# rgb-led-a.net
KiCad netlist of a schematic drawn in EAGLE
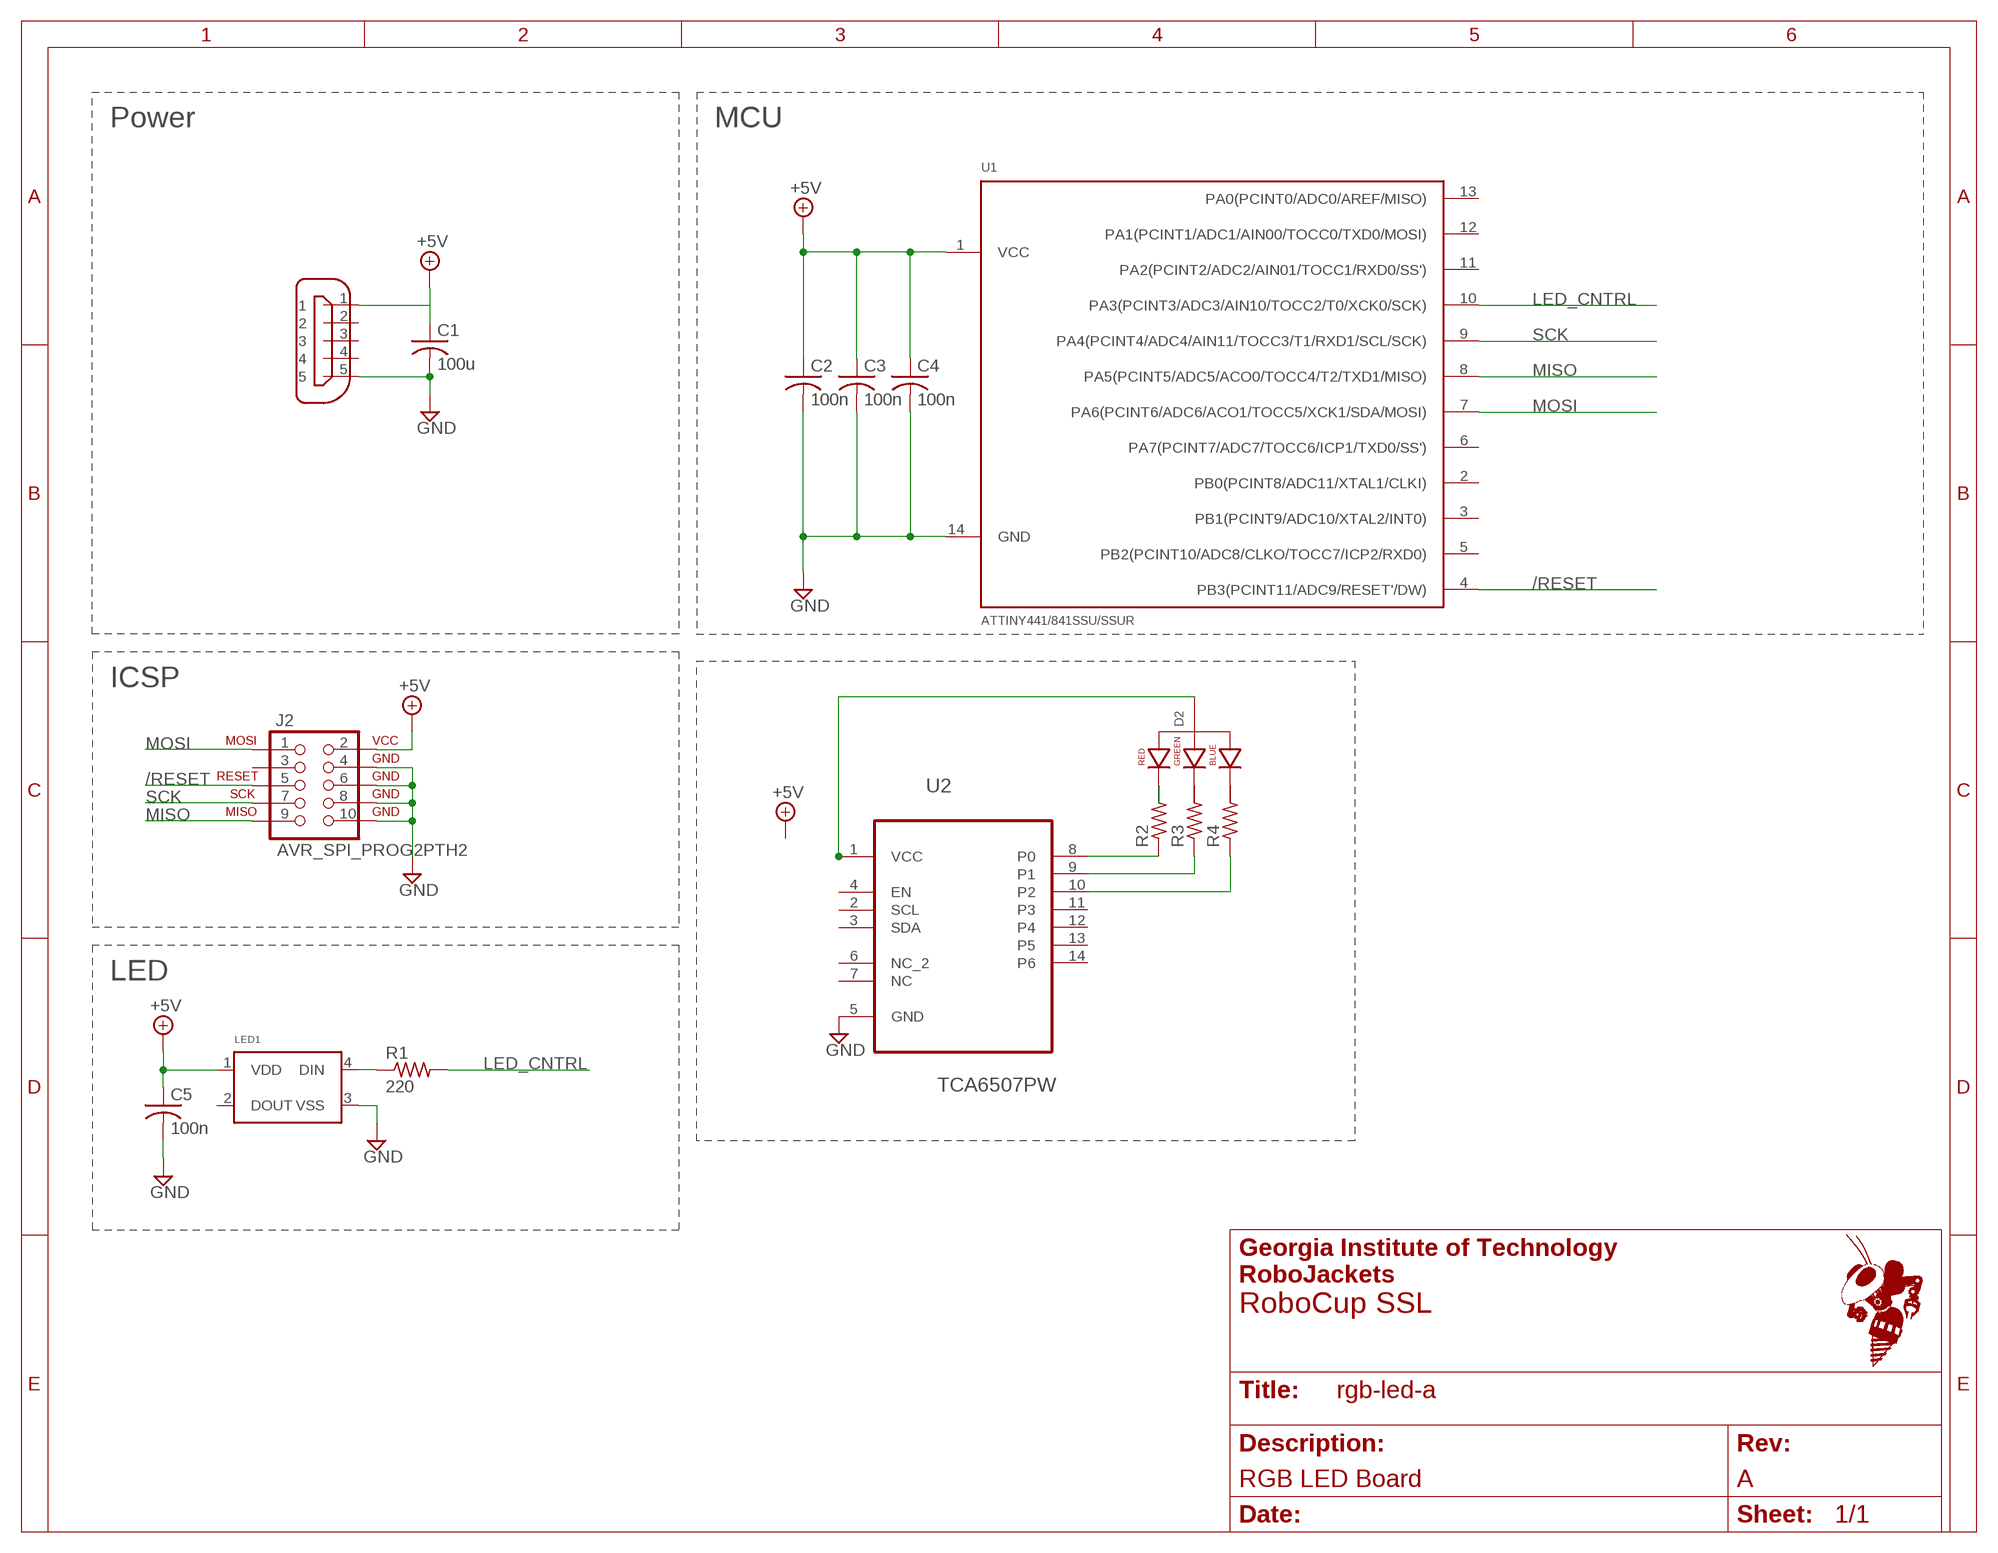
[diagram p0: schematic, sheet 1]

(export (version "E")
  (design (tool "Eeschema 10.0.6"))
  (components
    (comp (ref "C1")
      (value "100u")
      (footprint "eagle-import:C1206")
      (libsource (lib "eagle-import") (part "C-USC1206"))
    )
    (comp (ref "C2")
      (value "100n")
      (footprint "eagle-import:C0603")
      (libsource (lib "eagle-import") (part "C-USC0603"))
    )
    (comp (ref "C3")
      (value "100n")
      (footprint "eagle-import:C0603")
      (libsource (lib "eagle-import") (part "C-USC0603"))
    )
    (comp (ref "C4")
      (value "100n")
      (footprint "eagle-import:C0603")
      (libsource (lib "eagle-import") (part "C-USC0603"))
    )
    (comp (ref "C5")
      (value "100n")
      (footprint "eagle-import:C0603")
      (libsource (lib "eagle-import") (part "C-USC0603"))
    )
    (comp (ref "D2")
      (value "LED-RGB-CA-THRUCLEAR")
      (footprint "eagle-import:LED-RGB-THRU")
      (libsource (lib "eagle-import") (part "LED-RGB-CA-THRUCLEAR"))
    )
    (comp (ref "J1")
      (value "MICRO-USB")
      (footprint "eagle-import:GS-14-2180")
      (libsource (lib "eagle-import") (part "MICRO-USB"))
    )
    (comp (ref "J2")
      (value "AVR_SPI_PROG2PTH2")
      (footprint "eagle-import:2X5-SHROUDED")
      (libsource (lib "eagle-import") (part "AVR_SPI_PROG2PTH2"))
    )
    (comp (ref "LED1")
      (value "WS2812B")
      (footprint "eagle-import:5050")
      (libsource (lib "eagle-import") (part "WS2812B"))
    )
    (comp (ref "R1")
      (value "220")
      (footprint "eagle-import:R0603")
      (libsource (lib "eagle-import") (part "R-US_R0603"))
    )
    (comp (ref "R2")
      (value "R-US_R0805")
      (footprint "eagle-import:R0805")
      (libsource (lib "eagle-import") (part "resistor_R-US_R0805"))
    )
    (comp (ref "R3")
      (value "R-US_R0805")
      (footprint "eagle-import:R0805")
      (libsource (lib "eagle-import") (part "resistor_R-US_R0805"))
    )
    (comp (ref "R4")
      (value "R-US_R0805")
      (footprint "eagle-import:R0805")
      (libsource (lib "eagle-import") (part "resistor_R-US_R0805"))
    )
    (comp (ref "U1")
      (value "ATTINY441/841SSU/SSUR")
      (footprint "eagle-import:SOIC-14")
      (libsource (lib "eagle-import") (part "ATTINY441/841SSU/SSUR"))
    )
    (comp (ref "U2")
      (value "TCA6507PW")
      (footprint "eagle-import:SOP65P640X120-14N")
      (libsource (lib "eagle-import") (part "TCA6507PW"))
    )
  )
  (nets
    (net (code "1") (name "+5V") (class "Default")
      (node (ref "C1") (pin "1") (pinfunction "1_1") (pintype "passive"))
      (node (ref "C2") (pin "1") (pinfunction "1_1") (pintype "passive"))
      (node (ref "C3") (pin "1") (pinfunction "1_1") (pintype "passive"))
      (node (ref "C4") (pin "1") (pinfunction "1_1") (pintype "passive"))
      (node (ref "C5") (pin "1") (pinfunction "1_1") (pintype "passive"))
      (node (ref "J1") (pin "1") (pinfunction "1_1") (pintype "bidirectional"))
      (node (ref "J2") (pin "2") (pinfunction "VCC_2") (pintype "power_in"))
      (node (ref "LED1") (pin "1") (pinfunction "VDD_1") (pintype "bidirectional"))
      (node (ref "U1") (pin "1") (pinfunction "VCC_1") (pintype "bidirectional"))
    )
    (net (code "2") (name "/LED_CNTRL") (class "Default")
      (node (ref "R1") (pin "2") (pinfunction "2_2") (pintype "passive"))
      (node (ref "U1") (pin "10") (pinfunction "PA3(PCINT3/ADC3/AIN10/TOCC2/T0/XCK0/SCK)_10") (pintype "bidirectional"))
    )
    (net (code "3") (name "/MISO") (class "Default")
      (node (ref "J2") (pin "9") (pinfunction "MISO_9") (pintype "passive"))
      (node (ref "U1") (pin "8") (pinfunction "PA5(PCINT5/ADC5/ACO0/TOCC4/T2/TXD1/MISO)_8") (pintype "bidirectional"))
    )
    (net (code "4") (name "/MOSI") (class "Default")
      (node (ref "J2") (pin "1") (pinfunction "MOSI_1") (pintype "passive"))
      (node (ref "U1") (pin "7") (pinfunction "PA6(PCINT6/ADC6/ACO1/TOCC5/XCK1/SDA/MOSI)_7") (pintype "bidirectional"))
    )
    (net (code "5") (name "/SCK") (class "Default")
      (node (ref "J2") (pin "7") (pinfunction "SCK_7") (pintype "passive"))
      (node (ref "U1") (pin "9") (pinfunction "PA4(PCINT4/ADC4/AIN11/TOCC3/T1/RXD1/SCL/SCK)_9") (pintype "bidirectional"))
    )
    (net (code "6") (name "/{slash}RESET") (class "Default")
      (node (ref "J2") (pin "5") (pinfunction "RESET_5") (pintype "passive"))
      (node (ref "U1") (pin "4") (pinfunction "PB3(PCINT11/ADC9/RESET'/DW)_4") (pintype "bidirectional"))
    )
    (net (code "7") (name "GND") (class "Default")
      (node (ref "C1") (pin "2") (pinfunction "2_2") (pintype "passive"))
      (node (ref "C2") (pin "2") (pinfunction "2_2") (pintype "passive"))
      (node (ref "C3") (pin "2") (pinfunction "2_2") (pintype "passive"))
      (node (ref "C4") (pin "2") (pinfunction "2_2") (pintype "passive"))
      (node (ref "C5") (pin "2") (pinfunction "2_2") (pintype "passive"))
      (node (ref "J1") (pin "5") (pinfunction "5_5") (pintype "bidirectional"))
      (node (ref "J2") (pin "10") (pinfunction "GND_10") (pintype "power_in"))
      (node (ref "J2") (pin "4") (pinfunction "GND_4") (pintype "power_in"))
      (node (ref "J2") (pin "6") (pinfunction "GND_6") (pintype "power_in"))
      (node (ref "J2") (pin "8") (pinfunction "GND_8") (pintype "power_in"))
      (node (ref "LED1") (pin "3") (pinfunction "VSS_3") (pintype "bidirectional"))
      (node (ref "U1") (pin "14") (pinfunction "GND_14") (pintype "bidirectional"))
      (node (ref "U2") (pin "5") (pinfunction "GND_5") (pintype "passive"))
    )
    (net (code "8") (name "Net-(D2-ANODE)") (class "Default")
      (node (ref "D2") (pin "2") (pinfunction "ANODE_2") (pintype "bidirectional"))
      (node (ref "U2") (pin "1") (pinfunction "VCC_1") (pintype "power_in"))
    )
    (net (code "9") (name "Net-(D2-RED_CATHODE)") (class "Default")
      (node (ref "D2") (pin "1") (pinfunction "RED_CATHODE_1") (pintype "bidirectional"))
      (node (ref "R2") (pin "2") (pinfunction "2_2") (pintype "passive"))
    )
    (net (code "10") (name "Net-(LED1-DIN)") (class "Default")
      (node (ref "LED1") (pin "4") (pinfunction "DIN_4") (pintype "bidirectional"))
      (node (ref "R1") (pin "1") (pinfunction "1_1") (pintype "passive"))
    )
    (net (code "11") (name "Net-(U2-P0)") (class "Default")
      (node (ref "R2") (pin "1") (pinfunction "1_1") (pintype "passive"))
      (node (ref "U2") (pin "8") (pinfunction "P0_8") (pintype "output"))
    )
    (net (code "12") (name "Net-(U2-P1)") (class "Default")
      (node (ref "R3") (pin "1") (pinfunction "1_1") (pintype "passive"))
      (node (ref "U2") (pin "9") (pinfunction "P1_9") (pintype "output"))
    )
    (net (code "13") (name "Net-(U2-P2)") (class "Default")
      (node (ref "R4") (pin "1") (pinfunction "1_1") (pintype "passive"))
      (node (ref "U2") (pin "10") (pinfunction "P2_10") (pintype "output"))
    )
    (net (code "14") (name "unconnected-(D2-BLUE_CATHODE-Pad4)") (class "Default")
      (node (ref "D2") (pin "4") (pinfunction "BLUE_CATHODE_4") (pintype "bidirectional"))
    )
    (net (code "15") (name "unconnected-(D2-GREEN_CATHODE-Pad3)") (class "Default")
      (node (ref "D2") (pin "3") (pinfunction "GREEN_CATHODE_3") (pintype "bidirectional"))
    )
    (net (code "16") (name "unconnected-(J1-Pad2)") (class "Default")
      (node (ref "J1") (pin "2") (pinfunction "2_2") (pintype "bidirectional"))
    )
    (net (code "17") (name "unconnected-(J1-Pad3)") (class "Default")
      (node (ref "J1") (pin "3") (pinfunction "3_3") (pintype "bidirectional"))
    )
    (net (code "18") (name "unconnected-(J1-Pad4)") (class "Default")
      (node (ref "J1") (pin "4") (pinfunction "4_4") (pintype "bidirectional"))
    )
    (net (code "19") (name "unconnected-(J2-NC-Pad3)") (class "Default")
      (node (ref "J2") (pin "3") (pinfunction "NC_3") (pintype "no_connect"))
    )
    (net (code "20") (name "unconnected-(LED1-DOUT-Pad2)") (class "Default")
      (node (ref "LED1") (pin "2") (pinfunction "DOUT_2") (pintype "bidirectional"))
    )
    (net (code "21") (name "unconnected-(R3-Pad2)") (class "Default")
      (node (ref "R3") (pin "2") (pinfunction "2_2") (pintype "passive"))
    )
    (net (code "22") (name "unconnected-(R4-Pad2)") (class "Default")
      (node (ref "R4") (pin "2") (pinfunction "2_2") (pintype "passive"))
    )
    (net (code "23") (name "unconnected-(U1-PA0(PCINT0{slash}ADC0{slash}AREF{slash}MISO)-Pad13)") (class "Default")
      (node (ref "U1") (pin "13") (pinfunction "PA0(PCINT0/ADC0/AREF/MISO)_13") (pintype "bidirectional"))
    )
    (net (code "24") (name "unconnected-(U1-PA1(PCINT1{slash}ADC1{slash}AIN00{slash}TOCC0{slash}TXD0{slash}MOSI)-Pad12)") (class "Default")
      (node (ref "U1") (pin "12") (pinfunction "PA1(PCINT1/ADC1/AIN00/TOCC0/TXD0/MOSI)_12") (pintype "bidirectional"))
    )
    (net (code "25") (name "unconnected-(U1-PA2(PCINT2{slash}ADC2{slash}AIN01{slash}TOCC1{slash}RXD0{slash}SS')-Pad11)") (class "Default")
      (node (ref "U1") (pin "11") (pinfunction "PA2(PCINT2/ADC2/AIN01/TOCC1/RXD0/SS')_11") (pintype "bidirectional"))
    )
    (net (code "26") (name "unconnected-(U1-PA7(PCINT7{slash}ADC7{slash}TOCC6{slash}ICP1{slash}TXD0{slash}SS')-Pad6)") (class "Default")
      (node (ref "U1") (pin "6") (pinfunction "PA7(PCINT7/ADC7/TOCC6/ICP1/TXD0/SS')_6") (pintype "bidirectional"))
    )
    (net (code "27") (name "unconnected-(U1-PB0(PCINT8{slash}ADC11{slash}XTAL1{slash}CLKI)-Pad2)") (class "Default")
      (node (ref "U1") (pin "2") (pinfunction "PB0(PCINT8/ADC11/XTAL1/CLKI)_2") (pintype "bidirectional"))
    )
    (net (code "28") (name "unconnected-(U1-PB1(PCINT9{slash}ADC10{slash}XTAL2{slash}INT0)-Pad3)") (class "Default")
      (node (ref "U1") (pin "3") (pinfunction "PB1(PCINT9/ADC10/XTAL2/INT0)_3") (pintype "bidirectional"))
    )
    (net (code "29") (name "unconnected-(U1-PB2(PCINT10{slash}ADC8{slash}CLKO{slash}TOCC7{slash}ICP2{slash}RXD0)-Pad5)") (class "Default")
      (node (ref "U1") (pin "5") (pinfunction "PB2(PCINT10/ADC8/CLKO/TOCC7/ICP2/RXD0)_5") (pintype "bidirectional"))
    )
    (net (code "30") (name "unconnected-(U2-EN-Pad4)") (class "Default")
      (node (ref "U2") (pin "4") (pinfunction "EN_4") (pintype "input"))
    )
    (net (code "31") (name "unconnected-(U2-NC-Pad7)") (class "Default")
      (node (ref "U2") (pin "7") (pinfunction "NC_7") (pintype "no_connect"))
    )
    (net (code "32") (name "unconnected-(U2-NC_2-Pad6)") (class "Default")
      (node (ref "U2") (pin "6") (pinfunction "NC_2_6") (pintype "no_connect"))
    )
    (net (code "33") (name "unconnected-(U2-P3-Pad11)") (class "Default")
      (node (ref "U2") (pin "11") (pinfunction "P3_11") (pintype "output"))
    )
    (net (code "34") (name "unconnected-(U2-P4-Pad12)") (class "Default")
      (node (ref "U2") (pin "12") (pinfunction "P4_12") (pintype "output"))
    )
    (net (code "35") (name "unconnected-(U2-P5-Pad13)") (class "Default")
      (node (ref "U2") (pin "13") (pinfunction "P5_13") (pintype "output"))
    )
    (net (code "36") (name "unconnected-(U2-P6-Pad14)") (class "Default")
      (node (ref "U2") (pin "14") (pinfunction "P6_14") (pintype "output"))
    )
    (net (code "37") (name "unconnected-(U2-SCL-Pad2)") (class "Default")
      (node (ref "U2") (pin "2") (pinfunction "SCL_2") (pintype "input"))
    )
    (net (code "38") (name "unconnected-(U2-SDA-Pad3)") (class "Default")
      (node (ref "U2") (pin "3") (pinfunction "SDA_3") (pintype "input"))
    )
  )
)
